# esp32_LedTube.net
KiCad netlist of a schematic drawn in EAGLE
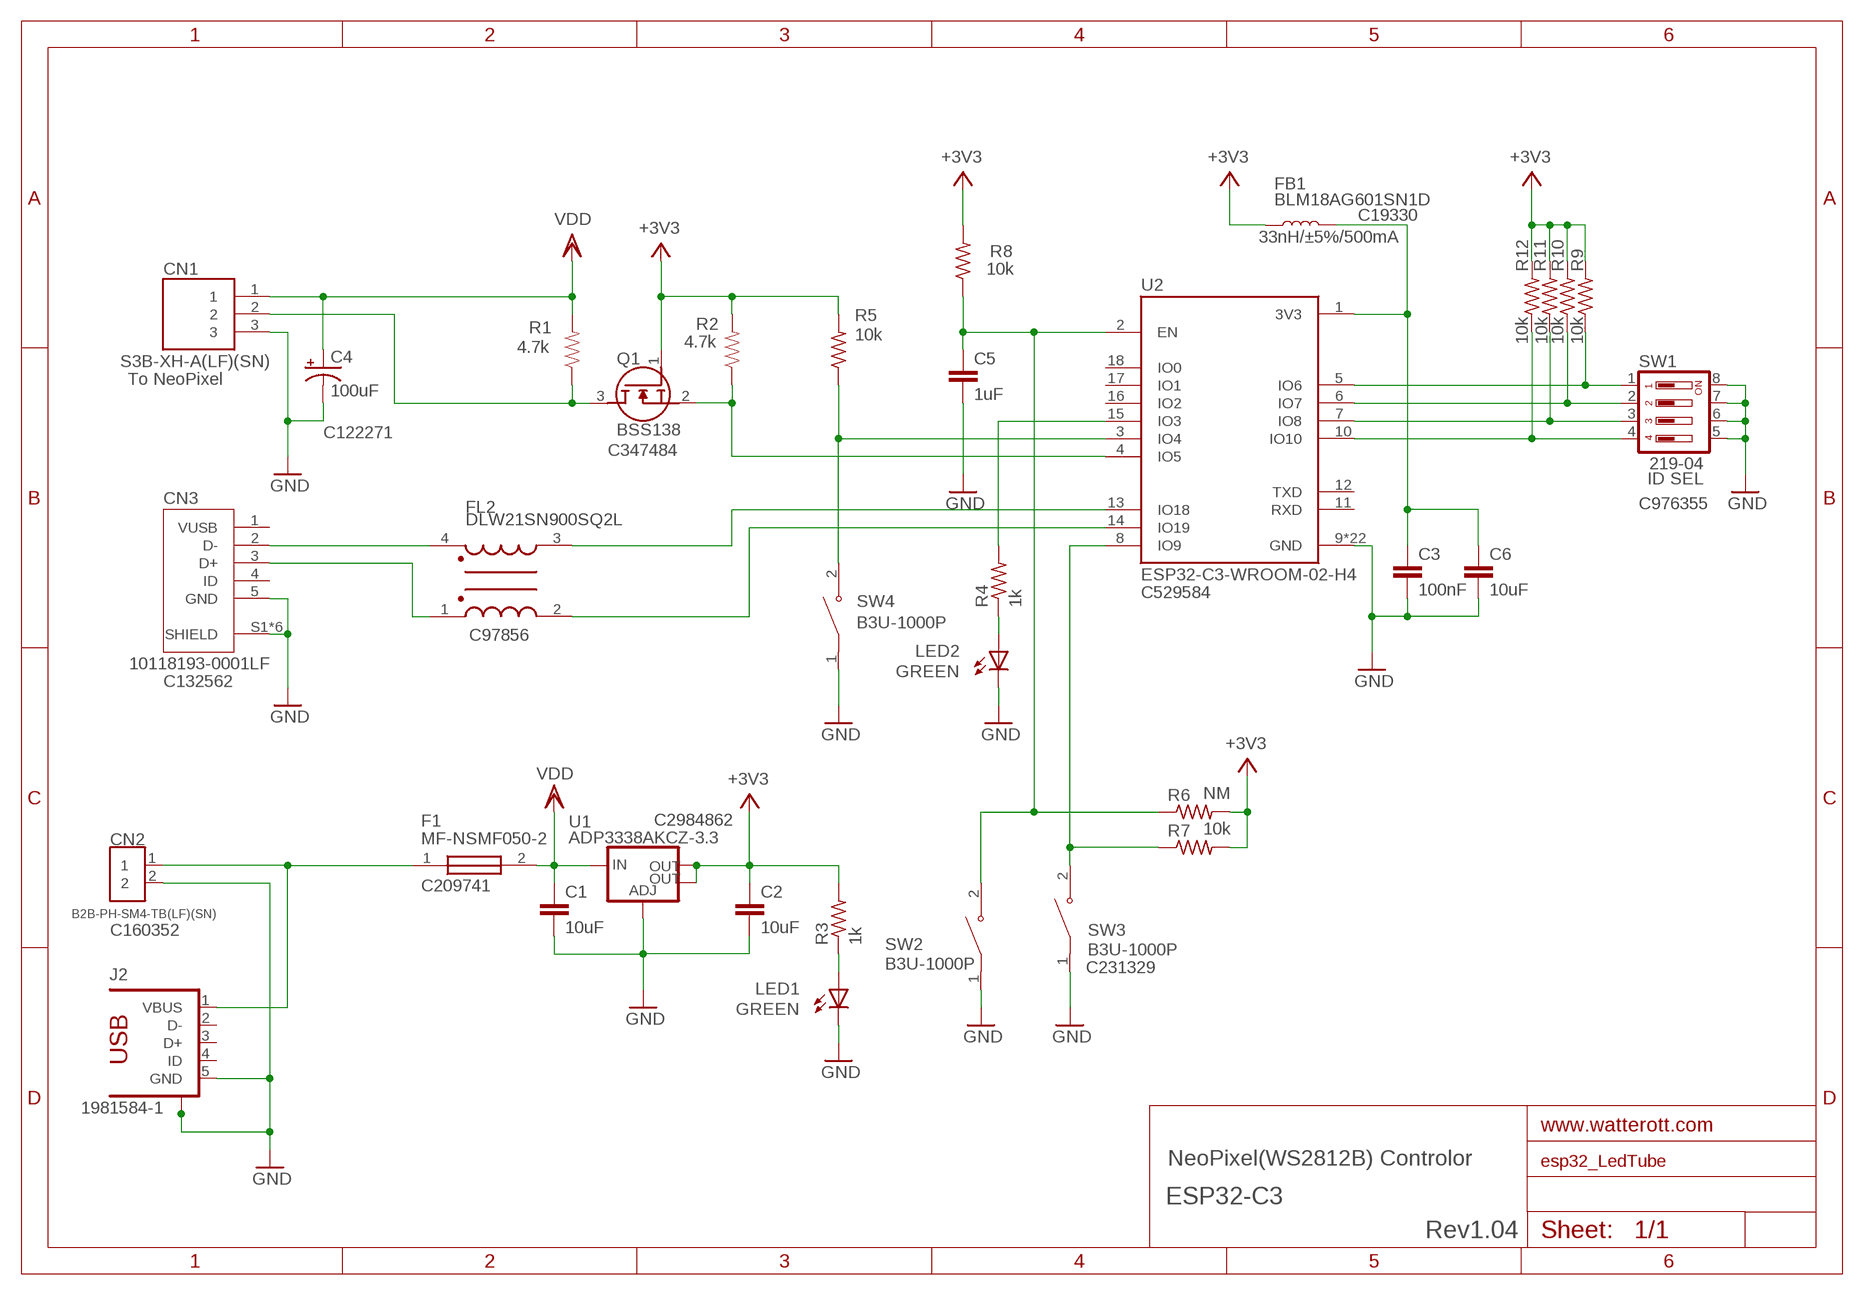
[diagram p0: schematic, sheet 1]

(export (version "E")
  (design (tool "Eeschema 10.0.6"))
  (components
    (comp (ref "C1")
      (value "10uF")
      (footprint "eagle-import:C0603")
      (libsource (lib "eagle-import") (part "C-EUC0603"))
    )
    (comp (ref "C2")
      (value "10uF")
      (footprint "eagle-import:C0603")
      (libsource (lib "eagle-import") (part "C-EUC0603"))
    )
    (comp (ref "C3")
      (value "100nF")
      (footprint "eagle-import:C0603")
      (libsource (lib "eagle-import") (part "C-EUC0603"))
    )
    (comp (ref "C4")
      (value "100uF")
      (footprint "eagle-import:B_3528-21R")
      (libsource (lib "eagle-import") (part "CPOL-USB/3528-21R"))
    )
    (comp (ref "C5")
      (value "1uF")
      (footprint "eagle-import:C0603")
      (libsource (lib "eagle-import") (part "C-EUC0603"))
    )
    (comp (ref "C6")
      (value "10uF")
      (footprint "eagle-import:C0603")
      (libsource (lib "eagle-import") (part "C-EUC0603"))
    )
    (comp (ref "CN1")
      (value "S3B-XH-A(LF)(SN)")
      (footprint "eagle-import:JST_S3B-XH-A(LF)(SN)")
      (fields (field (name "MF") "JST") (field (name "MP") "S3B-XH-A (LF)(SN)"))
      (libsource (lib "eagle-import") (part "S3B-XH-A(LF)(SN)"))
    )
    (comp (ref "CN2")
      (value "B2B-PH-SM4-TB(LF)(SN)")
      (footprint "eagle-import:JST_B2B-PH-SM4-TB(LF)(SN)")
      (fields
        (field (name "DIGI-KEY_PART_NUMBER") "455-1734-1-ND")
        (field (name "MF") "JST Sales")
        (field (name "MP") "B2B-PH-SM4-TB_LF__SN_")
      )
      (libsource (lib "eagle-import") (part "B2B-PH-SM4-TB(LF)(SN)"))
    )
    (comp (ref "CN3")
      (value "10118193-0001LF")
      (footprint "eagle-import:FCI_10118193-0001LF")
      (fields (field (name "MF") "FCI"))
      (libsource (lib "eagle-import") (part "10118193-0001LF"))
    )
    (comp (ref "F1")
      (value "MF-NSMF050-2")
      (footprint "eagle-import:FUSC3216X85N")
      (fields (field (name "MOUSER_PART_NUMBER") "652-MF-NSMF050-2"))
      (libsource (lib "eagle-import") (part "MF-NSMF050-2"))
    )
    (comp (ref "FB1")
      (value "33nH/±5%/500mA")
      (footprint "eagle-import:0603")
      (libsource (lib "eagle-import") (part "INDUCTOR-0603-33NH"))
    )
    (comp (ref "FL2")
      (value "DLW21SN900SQ2L")
      (footprint "eagle-import:FIL_DLW21SN900SQ2L")
      (fields (field (name "MF") "Murata"))
      (libsource (lib "eagle-import") (part "DLW21SN900SQ2L"))
    )
    (comp (ref "J2")
      (value "1981584-1")
      (footprint "eagle-import:1981584-1")
      (fields (field (name "MF") "Hirose") (field (name "MPN") "ZX62-AB-5PA(11) "))
      (libsource (lib "eagle-import") (part "1981584-1"))
    )
    (comp (ref "LED1")
      (value "GREEN")
      (footprint "eagle-import:CHIPLED_0603")
      (libsource (lib "eagle-import") (part "LEDCHIPLED_0603"))
    )
    (comp (ref "LED2")
      (value "GREEN")
      (footprint "eagle-import:CHIPLED_0603")
      (libsource (lib "eagle-import") (part "LEDCHIPLED_0603"))
    )
    (comp (ref "Q1")
      (value "BSS138")
      (footprint "eagle-import:SOT95P240X120-3N")
      (fields (field (name "MOUSER_PART_NUMBER") "512-BSS138"))
      (libsource (lib "eagle-import") (part "BSS138"))
    )
    (comp (ref "R1")
      (value "4.7k")
      (footprint "eagle-import:0603")
      (libsource (lib "eagle-import") (part "750OHM-0603-1/10W-1%"))
    )
    (comp (ref "R2")
      (value "4.7k")
      (footprint "eagle-import:0603")
      (libsource (lib "eagle-import") (part "750OHM-0603-1/10W-1%"))
    )
    (comp (ref "R3")
      (value "1k")
      (footprint "eagle-import:R0603")
      (libsource (lib "eagle-import") (part "R-US_R0603"))
    )
    (comp (ref "R4")
      (value "1k")
      (footprint "eagle-import:R0603")
      (libsource (lib "eagle-import") (part "R-US_R0603"))
    )
    (comp (ref "R5")
      (value "10k")
      (footprint "eagle-import:R0603")
      (libsource (lib "eagle-import") (part "R-US_R0603"))
    )
    (comp (ref "R6")
      (value "NM")
      (footprint "eagle-import:R0603")
      (libsource (lib "eagle-import") (part "R-US_R0603"))
    )
    (comp (ref "R7")
      (value "10k")
      (footprint "eagle-import:R0603")
      (libsource (lib "eagle-import") (part "R-US_R0603"))
    )
    (comp (ref "R8")
      (value "10k")
      (footprint "eagle-import:R0603")
      (libsource (lib "eagle-import") (part "R-US_R0603"))
    )
    (comp (ref "R9")
      (value "10k")
      (footprint "eagle-import:R0603")
      (libsource (lib "eagle-import") (part "R-US_R0603"))
    )
    (comp (ref "R10")
      (value "10k")
      (footprint "eagle-import:R0603")
      (libsource (lib "eagle-import") (part "R-US_R0603"))
    )
    (comp (ref "R11")
      (value "10k")
      (footprint "eagle-import:R0603")
      (libsource (lib "eagle-import") (part "R-US_R0603"))
    )
    (comp (ref "R12")
      (value "10k")
      (footprint "eagle-import:R0603")
      (libsource (lib "eagle-import") (part "R-US_R0603"))
    )
    (comp (ref "SW1")
      (value "219-04")
      (footprint "eagle-import:CTS-219-04")
      (libsource (lib "eagle-import") (part "219-04"))
    )
    (comp (ref "SW2")
      (value "B3U-1000P")
      (footprint "eagle-import:SW_B3U-1000P")
      (fields (field (name "MF") "Omron"))
      (libsource (lib "eagle-import") (part "B3U-1000P"))
    )
    (comp (ref "SW3")
      (value "B3U-1000P")
      (footprint "eagle-import:SW_B3U-1000P")
      (fields (field (name "MF") "Omron"))
      (libsource (lib "eagle-import") (part "B3U-1000P"))
    )
    (comp (ref "SW4")
      (value "B3U-1000P")
      (footprint "eagle-import:SW_B3U-1000P")
      (fields (field (name "MF") "Omron"))
      (libsource (lib "eagle-import") (part "B3U-1000P"))
    )
    (comp (ref "U1")
      (value "ADP3338AKCZ-3.3")
      (footprint "eagle-import:SOT223")
      (libsource (lib "eagle-import") (part "V_REG_LM1117SOT223"))
    )
    (comp (ref "U2")
      (value "ESP32-C3-WROOM-02-H4")
      (footprint "eagle-import:MODULE_ESP32-C3-WROOM-02-H4")
      (fields (field (name "MF") "Espressif Systems"))
      (libsource (lib "eagle-import") (part "ESP32-C3-WROOM-02-H4"))
    )
  )
  (nets
    (net (code "1") (name "+3V3") (class "Default")
      (node (ref "C2") (pin "1") (pinfunction "1_1") (pintype "passive"))
      (node (ref "FB1") (pin "1") (pinfunction "1_1") (pintype "passive"))
      (node (ref "Q1") (pin "1") (pinfunction "G_1") (pintype "bidirectional"))
      (node (ref "R10") (pin "2") (pinfunction "2_2") (pintype "passive"))
      (node (ref "R11") (pin "2") (pinfunction "2_2") (pintype "passive"))
      (node (ref "R12") (pin "2") (pinfunction "2_2") (pintype "passive"))
      (node (ref "R2") (pin "2") (pinfunction "2_2") (pintype "passive"))
      (node (ref "R3") (pin "2") (pinfunction "2_2") (pintype "passive"))
      (node (ref "R5") (pin "2") (pinfunction "2_2") (pintype "passive"))
      (node (ref "R6") (pin "2") (pinfunction "2_2") (pintype "passive"))
      (node (ref "R7") (pin "2") (pinfunction "2_2") (pintype "passive"))
      (node (ref "R8") (pin "2") (pinfunction "2_2") (pintype "passive"))
      (node (ref "R9") (pin "2") (pinfunction "2_2") (pintype "passive"))
      (node (ref "U1") (pin "2") (pinfunction "OUT_2") (pintype "output"))
      (node (ref "U1") (pin "4") (pinfunction "OUT_4") (pintype "output"))
    )
    (net (code "2") (name "GND") (class "Default")
      (node (ref "C1") (pin "2") (pinfunction "2_2") (pintype "passive"))
      (node (ref "C2") (pin "2") (pinfunction "2_2") (pintype "passive"))
      (node (ref "C3") (pin "2") (pinfunction "2_2") (pintype "passive"))
      (node (ref "C4") (pin "-") (pinfunction "-_-") (pintype "passive"))
      (node (ref "C5") (pin "2") (pinfunction "2_2") (pintype "passive"))
      (node (ref "C6") (pin "2") (pinfunction "2_2") (pintype "passive"))
      (node (ref "CN1") (pin "3") (pinfunction "3_3") (pintype "passive"))
      (node (ref "CN2") (pin "2") (pinfunction "2_2") (pintype "passive"))
      (node (ref "CN3") (pin "5") (pinfunction "GND_5") (pintype "passive"))
      (node (ref "CN3") (pin "S1") (pinfunction "SHIELD_S1") (pintype "passive"))
      (node (ref "CN3") (pin "S2") (pinfunction "SHIELD_S2") (pintype "passive"))
      (node (ref "CN3") (pin "S3") (pinfunction "SHIELD_S3") (pintype "passive"))
      (node (ref "CN3") (pin "S4") (pinfunction "SHIELD_S4") (pintype "passive"))
      (node (ref "CN3") (pin "S5") (pinfunction "SHIELD_S5") (pintype "passive"))
      (node (ref "CN3") (pin "S6") (pinfunction "SHIELD_S6") (pintype "passive"))
      (node (ref "J2") (pin "5") (pinfunction "GND_5") (pintype "passive"))
      (node (ref "J2") (pin "S1") (pinfunction "S1_S1") (pintype "passive"))
      (node (ref "J2") (pin "S2") (pinfunction "S2_S2") (pintype "passive"))
      (node (ref "J2") (pin "S3") (pinfunction "S3_S3") (pintype "passive"))
      (node (ref "J2") (pin "S4") (pinfunction "S4_S4") (pintype "passive"))
      (node (ref "LED1") (pin "C") (pinfunction "C_C") (pintype "passive"))
      (node (ref "LED2") (pin "C") (pinfunction "C_C") (pintype "passive"))
      (node (ref "SW1") (pin "5") (pinfunction "5_5") (pintype "passive"))
      (node (ref "SW1") (pin "6") (pinfunction "6_6") (pintype "passive"))
      (node (ref "SW1") (pin "7") (pinfunction "7_7") (pintype "passive"))
      (node (ref "SW1") (pin "8") (pinfunction "8_8") (pintype "passive"))
      (node (ref "SW2") (pin "1") (pinfunction "1_1") (pintype "passive"))
      (node (ref "SW3") (pin "1") (pinfunction "1_1") (pintype "passive"))
      (node (ref "SW4") (pin "1") (pinfunction "1_1") (pintype "passive"))
      (node (ref "U1") (pin "1") (pinfunction "ADJ_1") (pintype "input"))
      (node (ref "U2") (pin "19") (pinfunction "GND_19") (pintype "power_in"))
      (node (ref "U2") (pin "20") (pinfunction "GND_20") (pintype "power_in"))
      (node (ref "U2") (pin "21") (pinfunction "GND_21") (pintype "power_in"))
      (node (ref "U2") (pin "22") (pinfunction "GND_22") (pintype "power_in"))
      (node (ref "U2") (pin "23") (pinfunction "GND_23") (pintype "power_in"))
      (node (ref "U2") (pin "24") (pinfunction "GND_24") (pintype "power_in"))
      (node (ref "U2") (pin "25") (pinfunction "GND_25") (pintype "power_in"))
      (node (ref "U2") (pin "26") (pinfunction "GND_26") (pintype "power_in"))
      (node (ref "U2") (pin "27") (pinfunction "GND_27") (pintype "power_in"))
      (node (ref "U2") (pin "28") (pinfunction "GND_28") (pintype "power_in"))
      (node (ref "U2") (pin "29") (pinfunction "GND_29") (pintype "power_in"))
      (node (ref "U2") (pin "30") (pinfunction "GND_30") (pintype "power_in"))
      (node (ref "U2") (pin "31") (pinfunction "GND_31") (pintype "power_in"))
      (node (ref "U2") (pin "32") (pinfunction "GND_32") (pintype "power_in"))
      (node (ref "U2") (pin "33") (pinfunction "GND_33") (pintype "power_in"))
      (node (ref "U2") (pin "34") (pinfunction "GND_34") (pintype "power_in"))
      (node (ref "U2") (pin "35") (pinfunction "GND_35") (pintype "power_in"))
      (node (ref "U2") (pin "36") (pinfunction "GND_36") (pintype "power_in"))
      (node (ref "U2") (pin "37") (pinfunction "GND_37") (pintype "power_in"))
      (node (ref "U2") (pin "38") (pinfunction "GND_38") (pintype "power_in"))
      (node (ref "U2") (pin "39") (pinfunction "GND_39") (pintype "power_in"))
      (node (ref "U2") (pin "9") (pinfunction "GND_9") (pintype "power_in"))
    )
    (net (code "3") (name "Net-(CN3-D+)") (class "Default")
      (node (ref "CN3") (pin "3") (pinfunction "D+_3") (pintype "passive"))
      (node (ref "FL2") (pin "1") (pinfunction "1_1") (pintype "passive"))
    )
    (net (code "4") (name "Net-(CN3-D-)") (class "Default")
      (node (ref "CN3") (pin "2") (pinfunction "D-_2") (pintype "passive"))
      (node (ref "FL2") (pin "4") (pinfunction "4_4") (pintype "passive"))
    )
    (net (code "5") (name "Net-(J2-VBUS)") (class "Default")
      (node (ref "CN2") (pin "1") (pinfunction "1_1") (pintype "passive"))
      (node (ref "F1") (pin "1") (pinfunction "1_1") (pintype "bidirectional"))
      (node (ref "J2") (pin "1") (pinfunction "VBUS_1") (pintype "passive"))
    )
    (net (code "6") (name "Net-(LED1-PadA)") (class "Default")
      (node (ref "LED1") (pin "A") (pinfunction "A_A") (pintype "passive"))
      (node (ref "R3") (pin "1") (pinfunction "1_1") (pintype "passive"))
    )
    (net (code "7") (name "Net-(LED2-PadA)") (class "Default")
      (node (ref "LED2") (pin "A") (pinfunction "A_A") (pintype "passive"))
      (node (ref "R4") (pin "1") (pinfunction "1_1") (pintype "passive"))
    )
    (net (code "8") (name "Net-(Q1-D)") (class "Default")
      (node (ref "CN1") (pin "2") (pinfunction "2_2") (pintype "passive"))
      (node (ref "Q1") (pin "3") (pinfunction "D_3") (pintype "bidirectional"))
      (node (ref "R1") (pin "1") (pinfunction "1_1") (pintype "passive"))
    )
    (net (code "9") (name "Net-(Q1-S)") (class "Default")
      (node (ref "Q1") (pin "2") (pinfunction "S_2") (pintype "bidirectional"))
      (node (ref "R2") (pin "1") (pinfunction "1_1") (pintype "passive"))
      (node (ref "U2") (pin "4") (pinfunction "IO5_4") (pintype "bidirectional"))
    )
    (net (code "10") (name "Net-(U2-3V3)") (class "Default")
      (node (ref "C3") (pin "1") (pinfunction "1_1") (pintype "passive"))
      (node (ref "C6") (pin "1") (pinfunction "1_1") (pintype "passive"))
      (node (ref "FB1") (pin "2") (pinfunction "2_2") (pintype "passive"))
      (node (ref "U2") (pin "1") (pinfunction "3V3_1") (pintype "power_in"))
    )
    (net (code "11") (name "Net-(U2-EN)") (class "Default")
      (node (ref "C5") (pin "1") (pinfunction "1_1") (pintype "passive"))
      (node (ref "R6") (pin "1") (pinfunction "1_1") (pintype "passive"))
      (node (ref "R8") (pin "1") (pinfunction "1_1") (pintype "passive"))
      (node (ref "SW2") (pin "2") (pinfunction "2_2") (pintype "passive"))
      (node (ref "U2") (pin "2") (pinfunction "EN_2") (pintype "input"))
    )
    (net (code "12") (name "Net-(U2-IO3)") (class "Default")
      (node (ref "R4") (pin "2") (pinfunction "2_2") (pintype "passive"))
      (node (ref "U2") (pin "15") (pinfunction "IO3_15") (pintype "bidirectional"))
    )
    (net (code "13") (name "Net-(U2-IO4)") (class "Default")
      (node (ref "R5") (pin "1") (pinfunction "1_1") (pintype "passive"))
      (node (ref "SW4") (pin "2") (pinfunction "2_2") (pintype "passive"))
      (node (ref "U2") (pin "3") (pinfunction "IO4_3") (pintype "bidirectional"))
    )
    (net (code "14") (name "Net-(U2-IO6)") (class "Default")
      (node (ref "R9") (pin "1") (pinfunction "1_1") (pintype "passive"))
      (node (ref "SW1") (pin "1") (pinfunction "1_1") (pintype "passive"))
      (node (ref "U2") (pin "5") (pinfunction "IO6_5") (pintype "bidirectional"))
    )
    (net (code "15") (name "Net-(U2-IO7)") (class "Default")
      (node (ref "R10") (pin "1") (pinfunction "1_1") (pintype "passive"))
      (node (ref "SW1") (pin "2") (pinfunction "2_2") (pintype "passive"))
      (node (ref "U2") (pin "6") (pinfunction "IO7_6") (pintype "bidirectional"))
    )
    (net (code "16") (name "Net-(U2-IO8)") (class "Default")
      (node (ref "R11") (pin "1") (pinfunction "1_1") (pintype "passive"))
      (node (ref "SW1") (pin "3") (pinfunction "3_3") (pintype "passive"))
      (node (ref "U2") (pin "7") (pinfunction "IO8_7") (pintype "bidirectional"))
    )
    (net (code "17") (name "Net-(U2-IO9)") (class "Default")
      (node (ref "R7") (pin "1") (pinfunction "1_1") (pintype "passive"))
      (node (ref "SW3") (pin "2") (pinfunction "2_2") (pintype "passive"))
      (node (ref "U2") (pin "8") (pinfunction "IO9_8") (pintype "bidirectional"))
    )
    (net (code "18") (name "Net-(U2-IO10)") (class "Default")
      (node (ref "R12") (pin "1") (pinfunction "1_1") (pintype "passive"))
      (node (ref "SW1") (pin "4") (pinfunction "4_4") (pintype "passive"))
      (node (ref "U2") (pin "10") (pinfunction "IO10_10") (pintype "bidirectional"))
    )
    (net (code "19") (name "Net-(U2-IO18)") (class "Default")
      (node (ref "FL2") (pin "3") (pinfunction "3_3") (pintype "passive"))
      (node (ref "U2") (pin "13") (pinfunction "IO18_13") (pintype "bidirectional"))
    )
    (net (code "20") (name "Net-(U2-IO19)") (class "Default")
      (node (ref "FL2") (pin "2") (pinfunction "2_2") (pintype "passive"))
      (node (ref "U2") (pin "14") (pinfunction "IO19_14") (pintype "bidirectional"))
    )
    (net (code "21") (name "VDD") (class "Default")
      (node (ref "C1") (pin "1") (pinfunction "1_1") (pintype "passive"))
      (node (ref "C4") (pin "+") (pinfunction "+_+") (pintype "passive"))
      (node (ref "CN1") (pin "1") (pinfunction "1_1") (pintype "passive"))
      (node (ref "F1") (pin "2") (pinfunction "2_2") (pintype "bidirectional"))
      (node (ref "R1") (pin "2") (pinfunction "2_2") (pintype "passive"))
      (node (ref "U1") (pin "3") (pinfunction "IN_3") (pintype "input"))
    )
    (net (code "22") (name "unconnected-(CN3-ID-Pad4)") (class "Default")
      (node (ref "CN3") (pin "4") (pinfunction "ID_4") (pintype "passive"))
    )
    (net (code "23") (name "unconnected-(CN3-VUSB-Pad1)") (class "Default")
      (node (ref "CN3") (pin "1") (pinfunction "VUSB_1") (pintype "passive"))
    )
    (net (code "24") (name "unconnected-(J2-D+-Pad3)") (class "Default")
      (node (ref "J2") (pin "3") (pinfunction "D+_3") (pintype "passive"))
    )
    (net (code "25") (name "unconnected-(J2-D--Pad2)") (class "Default")
      (node (ref "J2") (pin "2") (pinfunction "D-_2") (pintype "passive"))
    )
    (net (code "26") (name "unconnected-(J2-ID-Pad4)") (class "Default")
      (node (ref "J2") (pin "4") (pinfunction "ID_4") (pintype "passive"))
    )
    (net (code "27") (name "unconnected-(U2-IO0-Pad18)") (class "Default")
      (node (ref "U2") (pin "18") (pinfunction "IO0_18") (pintype "bidirectional"))
    )
    (net (code "28") (name "unconnected-(U2-IO1-Pad17)") (class "Default")
      (node (ref "U2") (pin "17") (pinfunction "IO1_17") (pintype "bidirectional"))
    )
    (net (code "29") (name "unconnected-(U2-IO2-Pad16)") (class "Default")
      (node (ref "U2") (pin "16") (pinfunction "IO2_16") (pintype "bidirectional"))
    )
    (net (code "30") (name "unconnected-(U2-RXD-Pad11)") (class "Default")
      (node (ref "U2") (pin "11") (pinfunction "RXD_11") (pintype "bidirectional"))
    )
    (net (code "31") (name "unconnected-(U2-TXD-Pad12)") (class "Default")
      (node (ref "U2") (pin "12") (pinfunction "TXD_12") (pintype "bidirectional"))
    )
  )
)
